# main.net
KiCad netlist of a schematic drawn in EAGLE
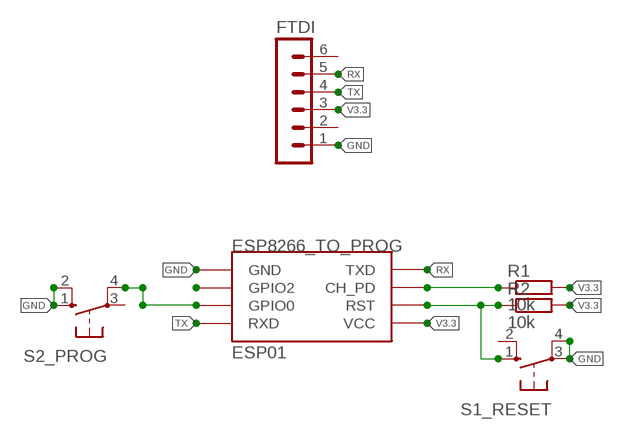
[diagram p0: schematic, sheet 1]

(export (version "E")
  (design (tool "Eeschema 10.0.6"))
  (components
    (comp (ref "ESP8266_TO_PROG")
      (value "ESP01")
      (footprint "eagle-import:ESP01")
      (libsource (lib "eagle-import") (part "ESP01"))
    )
    (comp (ref "FTDI")
      (value "MA06-1")
      (footprint "eagle-import:MA06-1")
      (libsource (lib "eagle-import") (part "MA06-1"))
    )
    (comp (ref "R1")
      (value "10k")
      (footprint "eagle-import:0204_7")
      (libsource (lib "eagle-import") (part "R-EU_0204/7"))
    )
    (comp (ref "R2")
      (value "10k")
      (footprint "eagle-import:0204_7")
      (libsource (lib "eagle-import") (part "R-EU_0204/7"))
    )
    (comp (ref "S1_RESET")
      (value "10-XX")
      (footprint "eagle-import:B3F-10XX")
      (fields (field (name "MPN") "B3F-1000"))
      (libsource (lib "eagle-import") (part "10-XX"))
    )
    (comp (ref "S2_PROG")
      (value "10-XX")
      (footprint "eagle-import:B3F-10XX")
      (fields (field (name "MPN") "B3F-1000"))
      (libsource (lib "eagle-import") (part "10-XX"))
    )
  )
  (nets
    (net (code "1") (name "GND") (class "Default")
      (node (ref "ESP8266_TO_PROG") (pin "GND") (pinfunction "GND_GND") (pintype "bidirectional"))
      (node (ref "FTDI") (pin "1") (pinfunction "1_1") (pintype "passive"))
      (node (ref "S1_RESET") (pin "3") (pinfunction "P_3") (pintype "passive"))
      (node (ref "S1_RESET") (pin "4") (pinfunction "P1_4") (pintype "passive"))
      (node (ref "S2_PROG") (pin "1") (pinfunction "S_1") (pintype "passive"))
      (node (ref "S2_PROG") (pin "2") (pinfunction "S1_2") (pintype "passive"))
    )
    (net (code "2") (name "Net-(ESP8266_TO_PROG-PadCH_PD)") (class "Default")
      (node (ref "ESP8266_TO_PROG") (pin "CH_PD") (pinfunction "CH_PD_CH_PD") (pintype "bidirectional"))
      (node (ref "R1") (pin "1") (pinfunction "1_1") (pintype "passive"))
    )
    (net (code "3") (name "Net-(S1_RESET-S)") (class "Default")
      (node (ref "ESP8266_TO_PROG") (pin "RST") (pinfunction "RST_RST") (pintype "bidirectional"))
      (node (ref "R2") (pin "1") (pinfunction "1_1") (pintype "passive"))
      (node (ref "S1_RESET") (pin "1") (pinfunction "S_1") (pintype "passive"))
    )
    (net (code "4") (name "Net-(S2_PROG-P1)") (class "Default")
      (node (ref "ESP8266_TO_PROG") (pin "GPIO0") (pinfunction "GPIO0_GPIO0") (pintype "bidirectional"))
      (node (ref "S2_PROG") (pin "4") (pinfunction "P1_4") (pintype "passive"))
    )
    (net (code "5") (name "RX") (class "Default")
      (node (ref "ESP8266_TO_PROG") (pin "TX") (pinfunction "TXD_TX") (pintype "bidirectional"))
      (node (ref "FTDI") (pin "5") (pinfunction "5_5") (pintype "passive"))
    )
    (net (code "6") (name "TX") (class "Default")
      (node (ref "ESP8266_TO_PROG") (pin "RX") (pinfunction "RXD_RX") (pintype "bidirectional"))
      (node (ref "FTDI") (pin "4") (pinfunction "4_4") (pintype "passive"))
    )
    (net (code "7") (name "V3.3") (class "Default")
      (node (ref "ESP8266_TO_PROG") (pin "VCC") (pinfunction "VCC_VCC") (pintype "bidirectional"))
      (node (ref "FTDI") (pin "3") (pinfunction "3_3") (pintype "passive"))
      (node (ref "R1") (pin "2") (pinfunction "2_2") (pintype "passive"))
      (node (ref "R2") (pin "2") (pinfunction "2_2") (pintype "passive"))
    )
    (net (code "8") (name "unconnected-(ESP8266_TO_PROG-PadGPIO2)") (class "Default")
      (node (ref "ESP8266_TO_PROG") (pin "GPIO2") (pinfunction "GPIO2_GPIO2") (pintype "bidirectional"))
    )
    (net (code "9") (name "unconnected-(FTDI-Pad2)") (class "Default")
      (node (ref "FTDI") (pin "2") (pinfunction "2_2") (pintype "passive"))
    )
    (net (code "10") (name "unconnected-(FTDI-Pad6)") (class "Default")
      (node (ref "FTDI") (pin "6") (pinfunction "6_6") (pintype "passive"))
    )
    (net (code "11") (name "unconnected-(S1_RESET-S1-Pad2)") (class "Default")
      (node (ref "S1_RESET") (pin "2") (pinfunction "S1_2") (pintype "passive"))
    )
    (net (code "12") (name "unconnected-(S2_PROG-P-Pad3)") (class "Default")
      (node (ref "S2_PROG") (pin "3") (pinfunction "P_3") (pintype "passive"))
    )
  )
)
